# top.net
KiCad netlist of a schematic drawn in Altium Designer
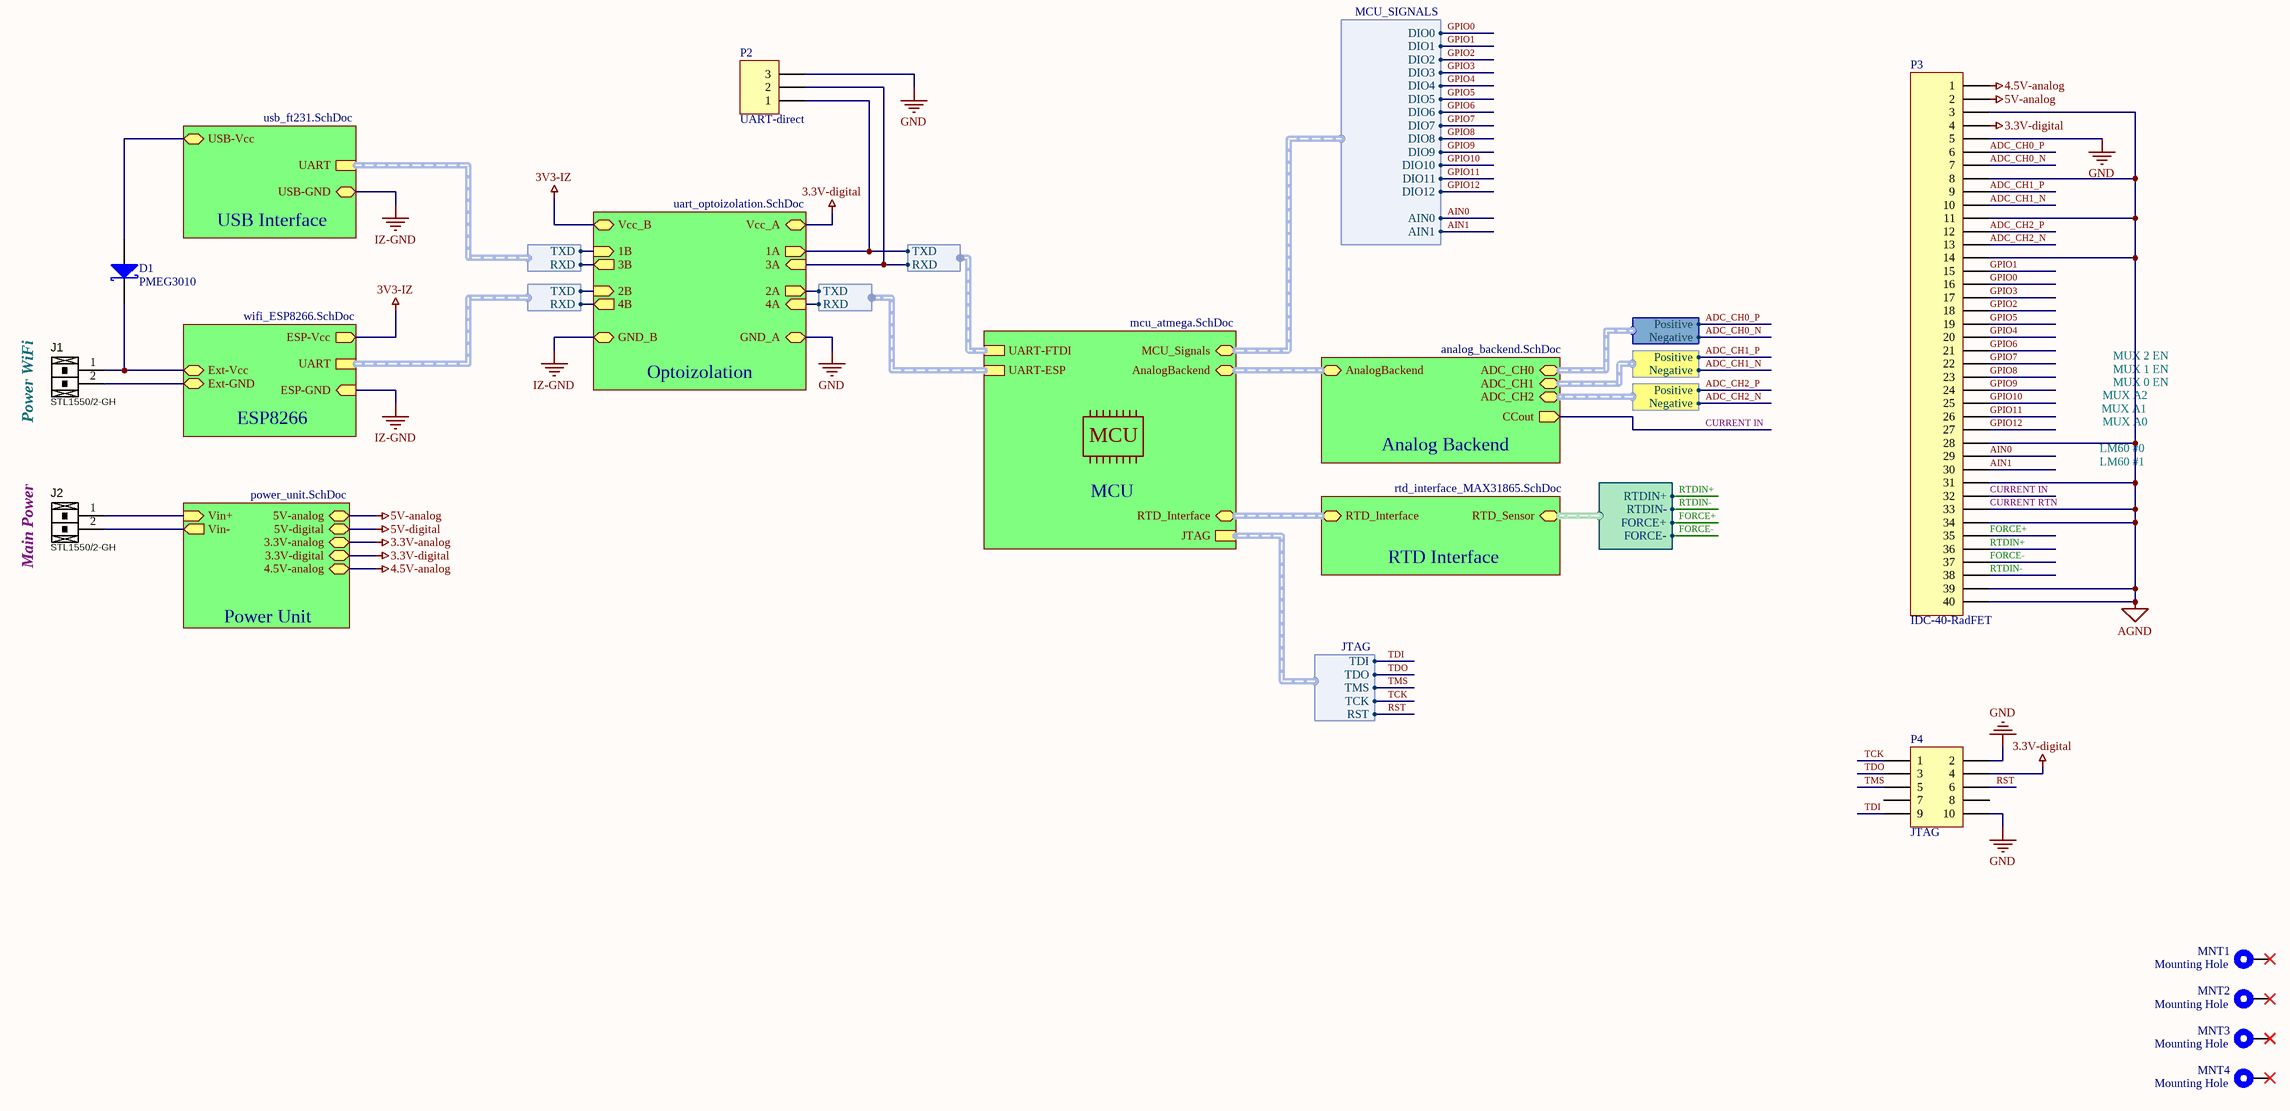
[diagram p0: top.SchDoc]

(export (version "E")
  (design (tool "Eeschema 10.0.6"))
  (components
    (comp (ref "D1")
      (value "PMEG3010")
      (footprint "SOD-323")
      (description "Schottky Rectifier")
      (libsource (lib "GG") (part "SchottkyX"))
    )
    (comp (ref "J1")
      (value "2P_TERM_BLOCK_HEADER")
      (footprint "2P_PCB_TERM_BLOCK_HDR_RA")
      (description "Terminal Block THT 2-position header 3.81mm pitch")
      (fields (field (name "MANUFACTURER PART NUMBER 1") "STL1550/2-GH"))
      (libsource (lib "GG") (part "2P_TERM_BLOCK_HEADER"))
    )
    (comp (ref "J2")
      (value "2P_TERM_BLOCK_HEADER")
      (footprint "2P_PCB_TERM_BLOCK_HDR_RA")
      (description "Terminal Block THT 2-position header 3.81mm pitch")
      (fields (field (name "MANUFACTURER PART NUMBER 1") "STL1550/2-GH"))
      (libsource (lib "GG") (part "2P_TERM_BLOCK_HEADER"))
    )
    (comp (ref "MNT1")
      (value "Mounting Hole")
      (footprint "PC-104_PcbMntHole_M3")
      (description "PCB Mounting Hole")
      (libsource (lib "connectors_printed-circuit-board") (part "MntHole"))
    )
    (comp (ref "MNT2")
      (value "Mounting Hole")
      (footprint "PC-104_PcbMntHole_M3")
      (description "PCB Mounting Hole")
      (libsource (lib "connectors_printed-circuit-board") (part "MntHole"))
    )
    (comp (ref "MNT3")
      (value "Mounting Hole")
      (footprint "PC-104_PcbMntHole_M3")
      (description "PCB Mounting Hole")
      (libsource (lib "connectors_printed-circuit-board") (part "MntHole"))
    )
    (comp (ref "MNT4")
      (value "Mounting Hole")
      (footprint "PC-104_PcbMntHole_M3")
      (description "PCB Mounting Hole")
      (libsource (lib "connectors_printed-circuit-board") (part "MntHole"))
    )
    (comp (ref "P2")
      (value "UART-direct")
      (footprint "HEADER 1X3 MALE")
      (description "Header, 3-Pin")
      (fields (field (name "PUBLISHER") "Altium Limited"))
      (libsource (lib "GG") (part "Header 3"))
    )
    (comp (ref "P3")
      (value "IDC-40-RadFET")
      (footprint "IDC-40-Male-Socket")
      (fields (field (name "PUBLISHER") "Altium Limited"))
      (libsource (lib "GG") (part "IDC-40-RadFET"))
    )
    (comp (ref "P4")
      (value "JTAG")
      (footprint "IDC-10-Male-Socket")
      (description "Header, 5-Pin, Dual row")
      (libsource (lib "GG") (part "Header 5X2"))
    )
  )
  (nets
    (net (code "7") (name "/1A") (class "Default")
      (node (ref "P2") (pin "1") (pinfunction "1_1") (pintype "passive"))
    )
    (net (code "11") (name "/3A") (class "Default")
      (node (ref "P2") (pin "2") (pinfunction "2_2") (pintype "passive"))
    )
    (net (code "15") (name "/ADC_CH0_N") (class "Default")
      (node (ref "P3") (pin "7") (pinfunction "7_7") (pintype "passive"))
    )
    (net (code "16") (name "/ADC_CH0_P") (class "Default")
      (node (ref "P3") (pin "6") (pinfunction "6_6") (pintype "passive"))
    )
    (net (code "17") (name "/ADC_CH1_N") (class "Default")
      (node (ref "P3") (pin "10") (pinfunction "10_10") (pintype "passive"))
    )
    (net (code "18") (name "/ADC_CH1_P") (class "Default")
      (node (ref "P3") (pin "9") (pinfunction "9_9") (pintype "passive"))
    )
    (net (code "19") (name "/ADC_CH2_N") (class "Default")
      (node (ref "P3") (pin "13") (pinfunction "13_13") (pintype "passive"))
    )
    (net (code "20") (name "/ADC_CH2_P") (class "Default")
      (node (ref "P3") (pin "12") (pinfunction "12_12") (pintype "passive"))
    )
    (net (code "21") (name "/AIN0") (class "Default")
      (node (ref "P3") (pin "29") (pinfunction "29_29") (pintype "passive"))
    )
    (net (code "22") (name "/AIN1") (class "Default")
      (node (ref "P3") (pin "30") (pinfunction "30_30") (pintype "passive"))
    )
    (net (code "24") (name "/CURRENT IN") (class "Default")
      (node (ref "P3") (pin "32") (pinfunction "32_32") (pintype "passive"))
    )
    (net (code "25") (name "/Ext-GND") (class "Default")
      (node (ref "J1") (pin "2") (pinfunction "2_2") (pintype "passive"))
    )
    (net (code "26") (name "/Ext-Vcc") (class "Default")
      (node (ref "D1") (pin "2") (pinfunction "K_2") (pintype "passive"))
      (node (ref "J1") (pin "1") (pinfunction "1_1") (pintype "passive"))
    )
    (net (code "27") (name "/FORCE+") (class "Default")
      (node (ref "P3") (pin "35") (pinfunction "35_35") (pintype "passive"))
    )
    (net (code "28") (name "/FORCE-") (class "Default")
      (node (ref "P3") (pin "37") (pinfunction "37_37") (pintype "passive"))
    )
    (net (code "29") (name "/GPIO0") (class "Default")
      (node (ref "P3") (pin "16") (pinfunction "16_16") (pintype "passive"))
    )
    (net (code "30") (name "/GPIO1") (class "Default")
      (node (ref "P3") (pin "15") (pinfunction "15_15") (pintype "passive"))
    )
    (net (code "31") (name "/GPIO2") (class "Default")
      (node (ref "P3") (pin "18") (pinfunction "18_18") (pintype "passive"))
    )
    (net (code "32") (name "/GPIO3") (class "Default")
      (node (ref "P3") (pin "17") (pinfunction "17_17") (pintype "passive"))
    )
    (net (code "33") (name "/GPIO4") (class "Default")
      (node (ref "P3") (pin "20") (pinfunction "20_20") (pintype "passive"))
    )
    (net (code "34") (name "/GPIO5") (class "Default")
      (node (ref "P3") (pin "19") (pinfunction "19_19") (pintype "passive"))
    )
    (net (code "35") (name "/GPIO6") (class "Default")
      (node (ref "P3") (pin "21") (pinfunction "21_21") (pintype "passive"))
    )
    (net (code "36") (name "/GPIO7") (class "Default")
      (node (ref "P3") (pin "22") (pinfunction "22_22") (pintype "passive"))
    )
    (net (code "37") (name "/GPIO8") (class "Default")
      (node (ref "P3") (pin "23") (pinfunction "23_23") (pintype "passive"))
    )
    (net (code "38") (name "/GPIO9") (class "Default")
      (node (ref "P3") (pin "24") (pinfunction "24_24") (pintype "passive"))
    )
    (net (code "39") (name "/GPIO10") (class "Default")
      (node (ref "P3") (pin "25") (pinfunction "25_25") (pintype "passive"))
    )
    (net (code "40") (name "/GPIO11") (class "Default")
      (node (ref "P3") (pin "26") (pinfunction "26_26") (pintype "passive"))
    )
    (net (code "41") (name "/GPIO12") (class "Default")
      (node (ref "P3") (pin "27") (pinfunction "27_27") (pintype "passive"))
    )
    (net (code "42") (name "/RST") (class "Default")
      (node (ref "P4") (pin "6") (pinfunction "6_6") (pintype "passive"))
    )
    (net (code "43") (name "/RTDIN+") (class "Default")
      (node (ref "P3") (pin "36") (pinfunction "36_36") (pintype "passive"))
    )
    (net (code "44") (name "/RTDIN-") (class "Default")
      (node (ref "P3") (pin "38") (pinfunction "38_38") (pintype "passive"))
    )
    (net (code "46") (name "/TCK") (class "Default")
      (node (ref "P4") (pin "1") (pinfunction "1_1") (pintype "passive"))
    )
    (net (code "47") (name "/TDI") (class "Default")
      (node (ref "P4") (pin "9") (pinfunction "9_9") (pintype "passive"))
    )
    (net (code "48") (name "/TDO") (class "Default")
      (node (ref "P4") (pin "3") (pinfunction "3_3") (pintype "passive"))
    )
    (net (code "49") (name "/TMS") (class "Default")
      (node (ref "P4") (pin "5") (pinfunction "5_5") (pintype "passive"))
    )
    (net (code "50") (name "/USB-Vcc") (class "Default")
      (node (ref "D1") (pin "1") (pinfunction "A_1") (pintype "passive"))
    )
    (net (code "51") (name "/Vin+") (class "Default")
      (node (ref "J2") (pin "1") (pinfunction "1_1") (pintype "passive"))
    )
    (net (code "52") (name "/Vin-") (class "Default")
      (node (ref "J2") (pin "2") (pinfunction "2_2") (pintype "passive"))
    )
    (net (code "59") (name "3.3V-digital") (class "Default")
      (node (ref "P3") (pin "4") (pinfunction "4_4") (pintype "passive"))
      (node (ref "P4") (pin "4") (pinfunction "4_4") (pintype "passive"))
    )
    (net (code "61") (name "4.5V-analog") (class "Default")
      (node (ref "P3") (pin "1") (pinfunction "1_1") (pintype "passive"))
    )
    (net (code "62") (name "5V-analog") (class "Default")
      (node (ref "P3") (pin "2") (pinfunction "2_2") (pintype "passive"))
    )
    (net (code "64") (name "AGND") (class "Default")
      (node (ref "P3") (pin "11") (pinfunction "11_11") (pintype "passive"))
      (node (ref "P3") (pin "14") (pinfunction "14_14") (pintype "passive"))
      (node (ref "P3") (pin "28") (pinfunction "28_28") (pintype "passive"))
      (node (ref "P3") (pin "3") (pinfunction "3_3") (pintype "passive"))
      (node (ref "P3") (pin "31") (pinfunction "31_31") (pintype "passive"))
      (node (ref "P3") (pin "33") (pinfunction "33_33") (pintype "passive"))
      (node (ref "P3") (pin "34") (pinfunction "34_34") (pintype "passive"))
      (node (ref "P3") (pin "39") (pinfunction "39_39") (pintype "passive"))
      (node (ref "P3") (pin "40") (pinfunction "40_40") (pintype "passive"))
      (node (ref "P3") (pin "8") (pinfunction "8_8") (pintype "passive"))
    )
    (net (code "65") (name "GND") (class "Default")
      (node (ref "P2") (pin "3") (pinfunction "3_3") (pintype "passive"))
      (node (ref "P3") (pin "5") (pinfunction "5_5") (pintype "passive"))
      (node (ref "P4") (pin "10") (pinfunction "10_10") (pintype "passive"))
      (node (ref "P4") (pin "2") (pinfunction "2_2") (pintype "passive"))
    )
    (net (code "67") (name "unconnected-(MNT1-Pad1)") (class "Default")
      (node (ref "MNT1") (pin "1") (pinfunction "1_1") (pintype "passive+no_connect"))
    )
    (net (code "68") (name "unconnected-(MNT2-Pad1)") (class "Default")
      (node (ref "MNT2") (pin "1") (pinfunction "1_1") (pintype "passive+no_connect"))
    )
    (net (code "69") (name "unconnected-(MNT3-Pad1)") (class "Default")
      (node (ref "MNT3") (pin "1") (pinfunction "1_1") (pintype "passive+no_connect"))
    )
    (net (code "70") (name "unconnected-(MNT4-Pad1)") (class "Default")
      (node (ref "MNT4") (pin "1") (pinfunction "1_1") (pintype "passive+no_connect"))
    )
    (net (code "71") (name "unconnected-(P4-Pad7)") (class "Default")
      (node (ref "P4") (pin "7") (pinfunction "7_7") (pintype "passive"))
    )
    (net (code "72") (name "unconnected-(P4-Pad8)") (class "Default")
      (node (ref "P4") (pin "8") (pinfunction "8_8") (pintype "passive"))
    )
  )
)
